# sch_THT.net
KiCad netlist of a schematic drawn in EAGLE
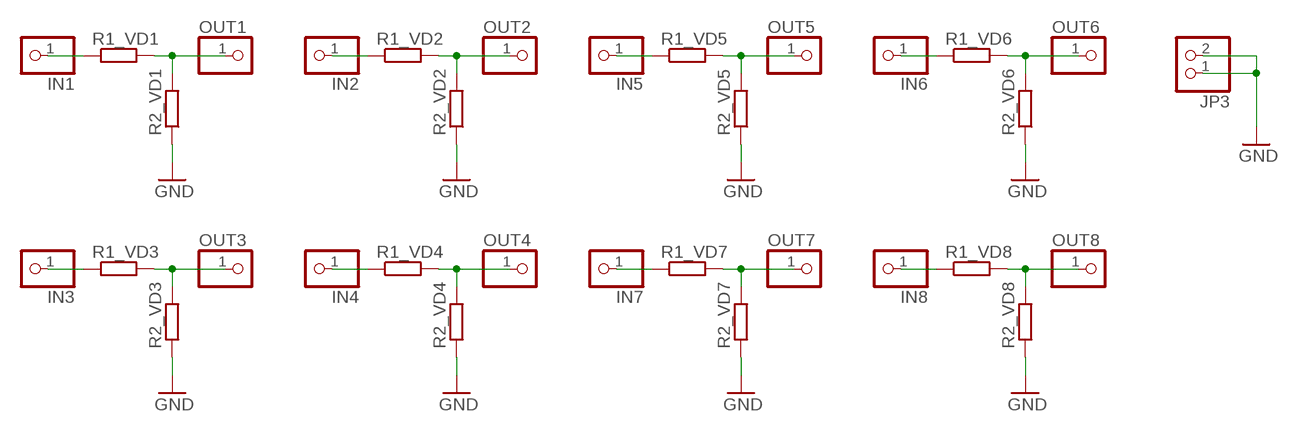
[diagram p0: schematic, sheet 1]

(export (version "E")
  (design (tool "Eeschema 10.0.6"))
  (components
    (comp (ref "IN1")
      (value "PINHD-1X1")
      (footprint "eagle-import:1X01")
      (libsource (lib "eagle-import") (part "PINHD-1X1"))
    )
    (comp (ref "IN2")
      (value "PINHD-1X1")
      (footprint "eagle-import:1X01")
      (libsource (lib "eagle-import") (part "PINHD-1X1"))
    )
    (comp (ref "IN3")
      (value "PINHD-1X1")
      (footprint "eagle-import:1X01")
      (libsource (lib "eagle-import") (part "PINHD-1X1"))
    )
    (comp (ref "IN4")
      (value "PINHD-1X1")
      (footprint "eagle-import:1X01")
      (libsource (lib "eagle-import") (part "PINHD-1X1"))
    )
    (comp (ref "IN5")
      (value "PINHD-1X1")
      (footprint "eagle-import:1X01")
      (libsource (lib "eagle-import") (part "PINHD-1X1"))
    )
    (comp (ref "IN6")
      (value "PINHD-1X1")
      (footprint "eagle-import:1X01")
      (libsource (lib "eagle-import") (part "PINHD-1X1"))
    )
    (comp (ref "IN7")
      (value "PINHD-1X1")
      (footprint "eagle-import:1X01")
      (libsource (lib "eagle-import") (part "PINHD-1X1"))
    )
    (comp (ref "IN8")
      (value "PINHD-1X1")
      (footprint "eagle-import:1X01")
      (libsource (lib "eagle-import") (part "PINHD-1X1"))
    )
    (comp (ref "JP3")
      (value "PINHD-1X2")
      (footprint "eagle-import:1X02")
      (libsource (lib "eagle-import") (part "PINHD-1X2"))
    )
    (comp (ref "OUT1")
      (value "PINHD-1X1")
      (footprint "eagle-import:1X01")
      (libsource (lib "eagle-import") (part "PINHD-1X1"))
    )
    (comp (ref "OUT2")
      (value "PINHD-1X1")
      (footprint "eagle-import:1X01")
      (libsource (lib "eagle-import") (part "PINHD-1X1"))
    )
    (comp (ref "OUT3")
      (value "PINHD-1X1")
      (footprint "eagle-import:1X01")
      (libsource (lib "eagle-import") (part "PINHD-1X1"))
    )
    (comp (ref "OUT4")
      (value "PINHD-1X1")
      (footprint "eagle-import:1X01")
      (libsource (lib "eagle-import") (part "PINHD-1X1"))
    )
    (comp (ref "OUT5")
      (value "PINHD-1X1")
      (footprint "eagle-import:1X01")
      (libsource (lib "eagle-import") (part "PINHD-1X1"))
    )
    (comp (ref "OUT6")
      (value "PINHD-1X1")
      (footprint "eagle-import:1X01")
      (libsource (lib "eagle-import") (part "PINHD-1X1"))
    )
    (comp (ref "OUT7")
      (value "PINHD-1X1")
      (footprint "eagle-import:1X01")
      (libsource (lib "eagle-import") (part "PINHD-1X1"))
    )
    (comp (ref "OUT8")
      (value "PINHD-1X1")
      (footprint "eagle-import:1X01")
      (libsource (lib "eagle-import") (part "PINHD-1X1"))
    )
    (comp (ref "R1_VD1")
      (value "R-EU_0204/7")
      (footprint "eagle-import:0204_7")
      (libsource (lib "eagle-import") (part "R-EU_0204/7"))
    )
    (comp (ref "R1_VD2")
      (value "R-EU_0204/7")
      (footprint "eagle-import:0204_7")
      (libsource (lib "eagle-import") (part "R-EU_0204/7"))
    )
    (comp (ref "R1_VD3")
      (value "R-EU_0204/7")
      (footprint "eagle-import:0204_7")
      (libsource (lib "eagle-import") (part "R-EU_0204/7"))
    )
    (comp (ref "R1_VD4")
      (value "R-EU_0204/7")
      (footprint "eagle-import:0204_7")
      (libsource (lib "eagle-import") (part "R-EU_0204/7"))
    )
    (comp (ref "R1_VD5")
      (value "R-EU_0204/7")
      (footprint "eagle-import:0204_7")
      (libsource (lib "eagle-import") (part "R-EU_0204/7"))
    )
    (comp (ref "R1_VD6")
      (value "R-EU_0204/7")
      (footprint "eagle-import:0204_7")
      (libsource (lib "eagle-import") (part "R-EU_0204/7"))
    )
    (comp (ref "R1_VD7")
      (value "R-EU_0204/7")
      (footprint "eagle-import:0204_7")
      (libsource (lib "eagle-import") (part "R-EU_0204/7"))
    )
    (comp (ref "R1_VD8")
      (value "R-EU_0204/7")
      (footprint "eagle-import:0204_7")
      (libsource (lib "eagle-import") (part "R-EU_0204/7"))
    )
    (comp (ref "R2_VD1")
      (value "R-EU_0204/7")
      (footprint "eagle-import:0204_7")
      (libsource (lib "eagle-import") (part "R-EU_0204/7"))
    )
    (comp (ref "R2_VD2")
      (value "R-EU_0204/7")
      (footprint "eagle-import:0204_7")
      (libsource (lib "eagle-import") (part "R-EU_0204/7"))
    )
    (comp (ref "R2_VD3")
      (value "R-EU_0204/7")
      (footprint "eagle-import:0204_7")
      (libsource (lib "eagle-import") (part "R-EU_0204/7"))
    )
    (comp (ref "R2_VD4")
      (value "R-EU_0204/7")
      (footprint "eagle-import:0204_7")
      (libsource (lib "eagle-import") (part "R-EU_0204/7"))
    )
    (comp (ref "R2_VD5")
      (value "R-EU_0204/7")
      (footprint "eagle-import:0204_7")
      (libsource (lib "eagle-import") (part "R-EU_0204/7"))
    )
    (comp (ref "R2_VD6")
      (value "R-EU_0204/7")
      (footprint "eagle-import:0204_7")
      (libsource (lib "eagle-import") (part "R-EU_0204/7"))
    )
    (comp (ref "R2_VD7")
      (value "R-EU_0204/7")
      (footprint "eagle-import:0204_7")
      (libsource (lib "eagle-import") (part "R-EU_0204/7"))
    )
    (comp (ref "R2_VD8")
      (value "R-EU_0204/7")
      (footprint "eagle-import:0204_7")
      (libsource (lib "eagle-import") (part "R-EU_0204/7"))
    )
  )
  (nets
    (net (code "1") (name "GND") (class "Default")
      (node (ref "JP3") (pin "1") (pinfunction "1_1") (pintype "passive"))
      (node (ref "JP3") (pin "2") (pinfunction "2_2") (pintype "passive"))
      (node (ref "R2_VD1") (pin "1") (pinfunction "1_1") (pintype "passive"))
      (node (ref "R2_VD2") (pin "1") (pinfunction "1_1") (pintype "passive"))
      (node (ref "R2_VD3") (pin "1") (pinfunction "1_1") (pintype "passive"))
      (node (ref "R2_VD4") (pin "1") (pinfunction "1_1") (pintype "passive"))
      (node (ref "R2_VD5") (pin "1") (pinfunction "1_1") (pintype "passive"))
      (node (ref "R2_VD6") (pin "1") (pinfunction "1_1") (pintype "passive"))
      (node (ref "R2_VD7") (pin "1") (pinfunction "1_1") (pintype "passive"))
      (node (ref "R2_VD8") (pin "1") (pinfunction "1_1") (pintype "passive"))
    )
    (net (code "2") (name "Net-(IN1-Pad1)") (class "Default")
      (node (ref "IN1") (pin "1") (pinfunction "1_1") (pintype "passive"))
      (node (ref "R1_VD1") (pin "1") (pinfunction "1_1") (pintype "passive"))
    )
    (net (code "3") (name "Net-(IN2-Pad1)") (class "Default")
      (node (ref "IN2") (pin "1") (pinfunction "1_1") (pintype "passive"))
      (node (ref "R1_VD2") (pin "1") (pinfunction "1_1") (pintype "passive"))
    )
    (net (code "4") (name "Net-(IN3-Pad1)") (class "Default")
      (node (ref "IN3") (pin "1") (pinfunction "1_1") (pintype "passive"))
      (node (ref "R1_VD3") (pin "1") (pinfunction "1_1") (pintype "passive"))
    )
    (net (code "5") (name "Net-(IN4-Pad1)") (class "Default")
      (node (ref "IN4") (pin "1") (pinfunction "1_1") (pintype "passive"))
      (node (ref "R1_VD4") (pin "1") (pinfunction "1_1") (pintype "passive"))
    )
    (net (code "6") (name "Net-(IN5-Pad1)") (class "Default")
      (node (ref "IN5") (pin "1") (pinfunction "1_1") (pintype "passive"))
      (node (ref "R1_VD5") (pin "1") (pinfunction "1_1") (pintype "passive"))
    )
    (net (code "7") (name "Net-(IN6-Pad1)") (class "Default")
      (node (ref "IN6") (pin "1") (pinfunction "1_1") (pintype "passive"))
      (node (ref "R1_VD6") (pin "1") (pinfunction "1_1") (pintype "passive"))
    )
    (net (code "8") (name "Net-(IN7-Pad1)") (class "Default")
      (node (ref "IN7") (pin "1") (pinfunction "1_1") (pintype "passive"))
      (node (ref "R1_VD7") (pin "1") (pinfunction "1_1") (pintype "passive"))
    )
    (net (code "9") (name "Net-(IN8-Pad1)") (class "Default")
      (node (ref "IN8") (pin "1") (pinfunction "1_1") (pintype "passive"))
      (node (ref "R1_VD8") (pin "1") (pinfunction "1_1") (pintype "passive"))
    )
    (net (code "10") (name "Net-(OUT1-Pad1)") (class "Default")
      (node (ref "OUT1") (pin "1") (pinfunction "1_1") (pintype "passive"))
      (node (ref "R1_VD1") (pin "2") (pinfunction "2_2") (pintype "passive"))
      (node (ref "R2_VD1") (pin "2") (pinfunction "2_2") (pintype "passive"))
    )
    (net (code "11") (name "Net-(OUT2-Pad1)") (class "Default")
      (node (ref "OUT2") (pin "1") (pinfunction "1_1") (pintype "passive"))
      (node (ref "R1_VD2") (pin "2") (pinfunction "2_2") (pintype "passive"))
      (node (ref "R2_VD2") (pin "2") (pinfunction "2_2") (pintype "passive"))
    )
    (net (code "12") (name "Net-(OUT3-Pad1)") (class "Default")
      (node (ref "OUT3") (pin "1") (pinfunction "1_1") (pintype "passive"))
      (node (ref "R1_VD3") (pin "2") (pinfunction "2_2") (pintype "passive"))
      (node (ref "R2_VD3") (pin "2") (pinfunction "2_2") (pintype "passive"))
    )
    (net (code "13") (name "Net-(OUT4-Pad1)") (class "Default")
      (node (ref "OUT4") (pin "1") (pinfunction "1_1") (pintype "passive"))
      (node (ref "R1_VD4") (pin "2") (pinfunction "2_2") (pintype "passive"))
      (node (ref "R2_VD4") (pin "2") (pinfunction "2_2") (pintype "passive"))
    )
    (net (code "14") (name "Net-(OUT5-Pad1)") (class "Default")
      (node (ref "OUT5") (pin "1") (pinfunction "1_1") (pintype "passive"))
      (node (ref "R1_VD5") (pin "2") (pinfunction "2_2") (pintype "passive"))
      (node (ref "R2_VD5") (pin "2") (pinfunction "2_2") (pintype "passive"))
    )
    (net (code "15") (name "Net-(OUT6-Pad1)") (class "Default")
      (node (ref "OUT6") (pin "1") (pinfunction "1_1") (pintype "passive"))
      (node (ref "R1_VD6") (pin "2") (pinfunction "2_2") (pintype "passive"))
      (node (ref "R2_VD6") (pin "2") (pinfunction "2_2") (pintype "passive"))
    )
    (net (code "16") (name "Net-(OUT7-Pad1)") (class "Default")
      (node (ref "OUT7") (pin "1") (pinfunction "1_1") (pintype "passive"))
      (node (ref "R1_VD7") (pin "2") (pinfunction "2_2") (pintype "passive"))
      (node (ref "R2_VD7") (pin "2") (pinfunction "2_2") (pintype "passive"))
    )
    (net (code "17") (name "Net-(OUT8-Pad1)") (class "Default")
      (node (ref "OUT8") (pin "1") (pinfunction "1_1") (pintype "passive"))
      (node (ref "R1_VD8") (pin "2") (pinfunction "2_2") (pintype "passive"))
      (node (ref "R2_VD8") (pin "2") (pinfunction "2_2") (pintype "passive"))
    )
  )
)
